# zx81_SD_12.net
KiCad netlist of a schematic drawn in EAGLE
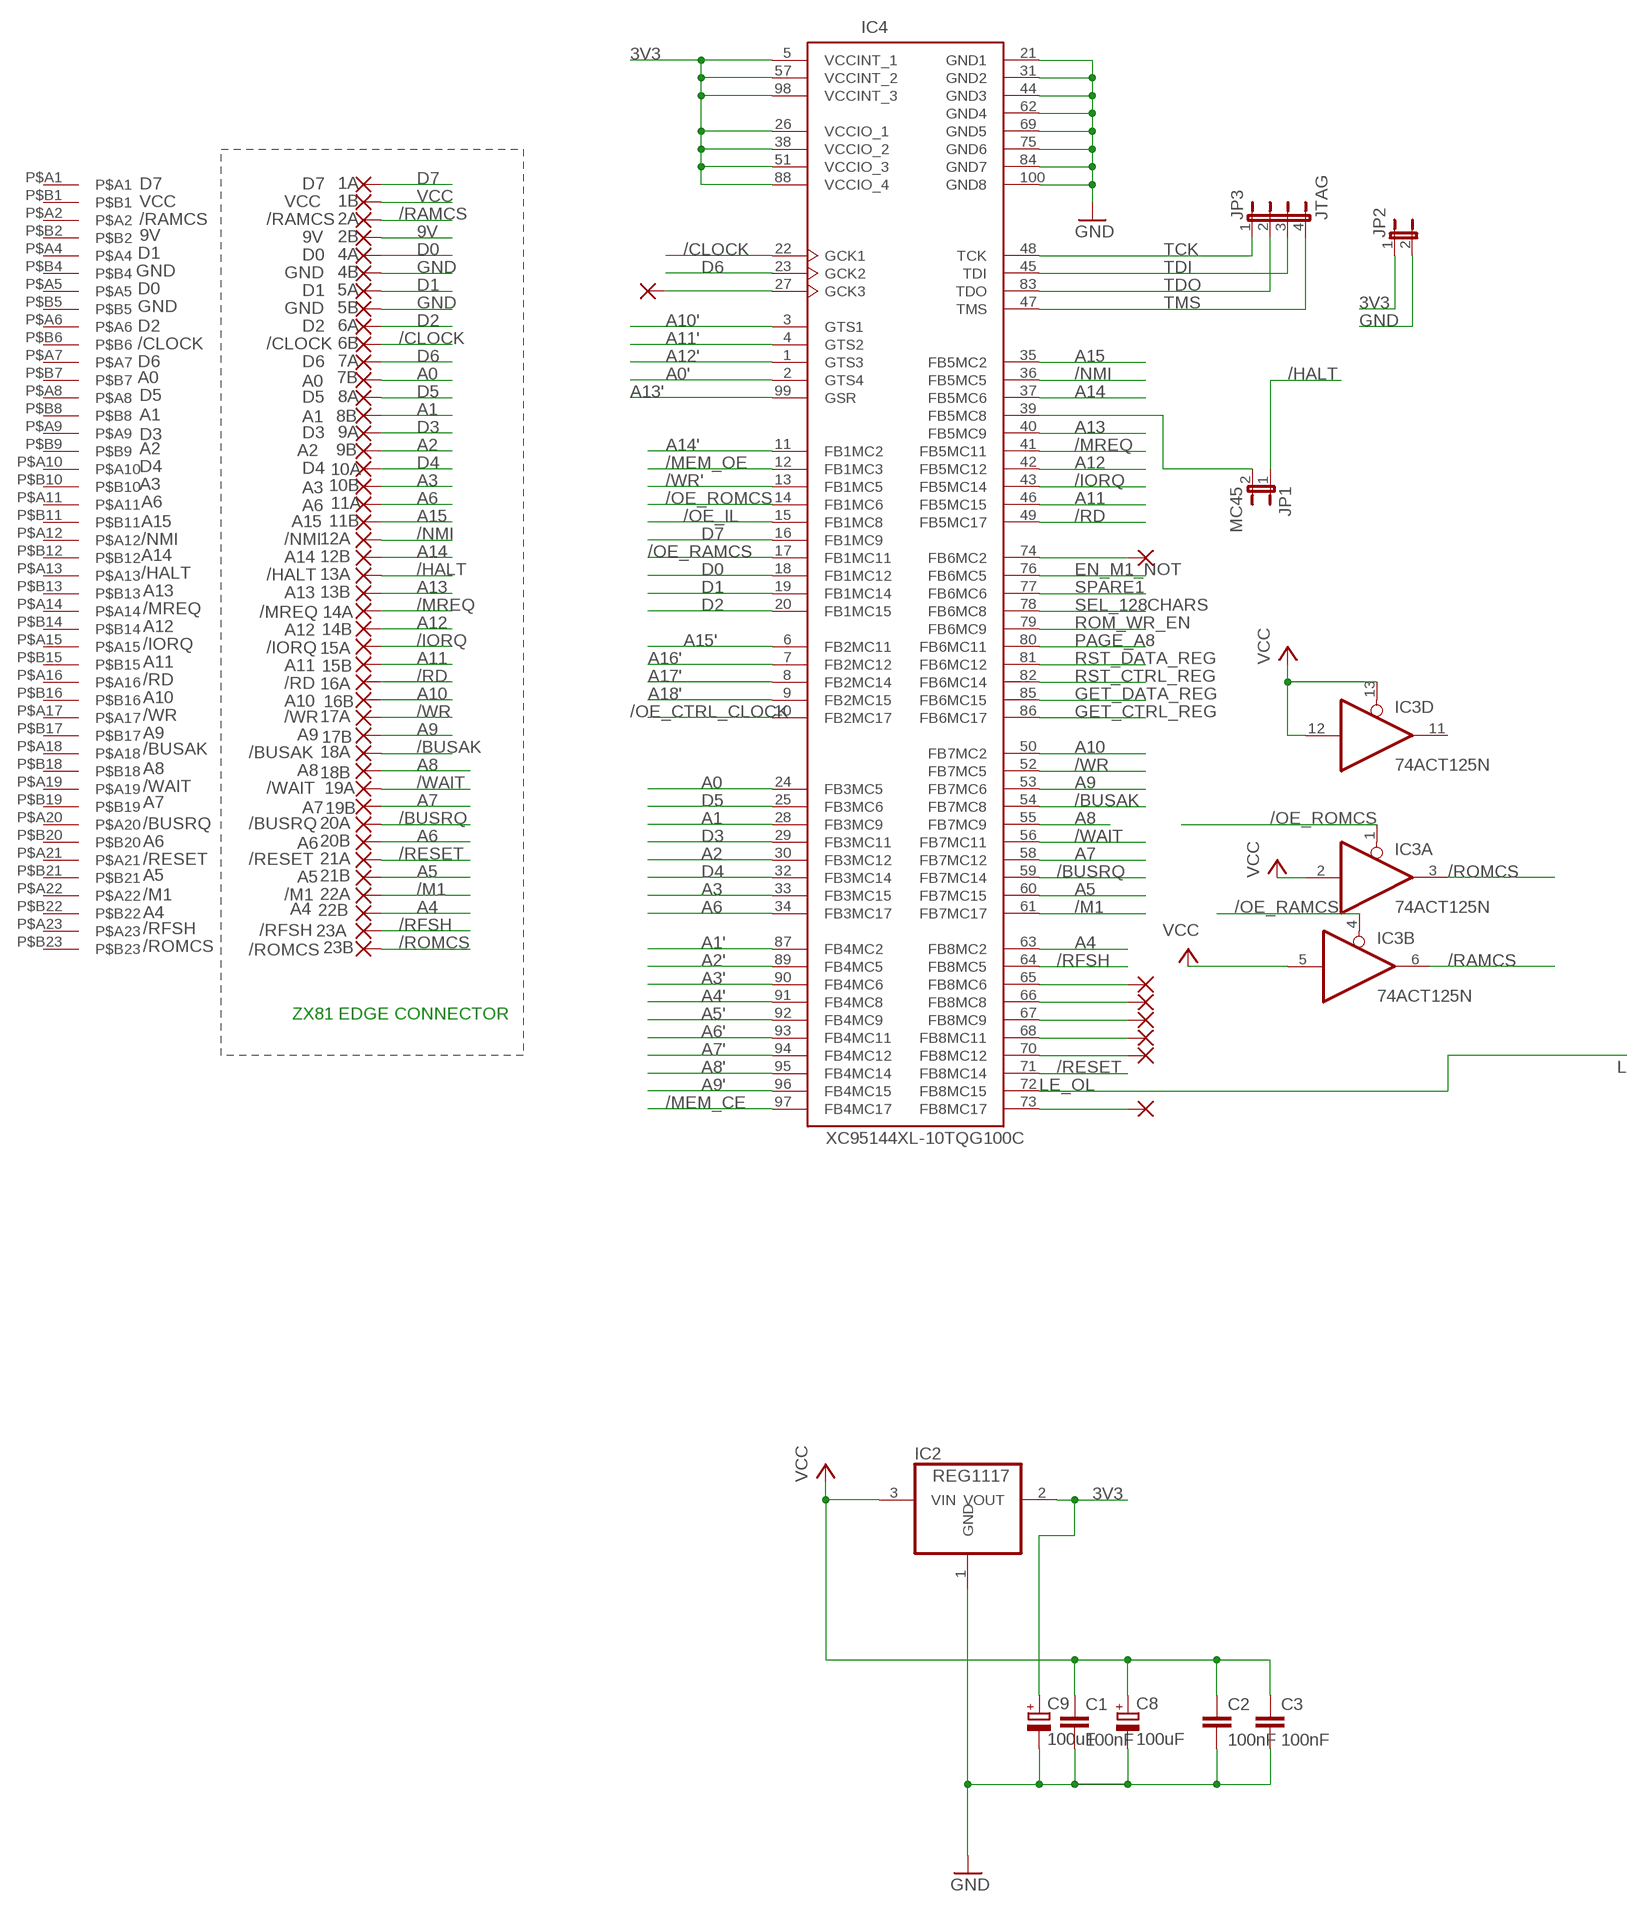
[diagram p0: schematic, sheet 1, part 1 of 2]
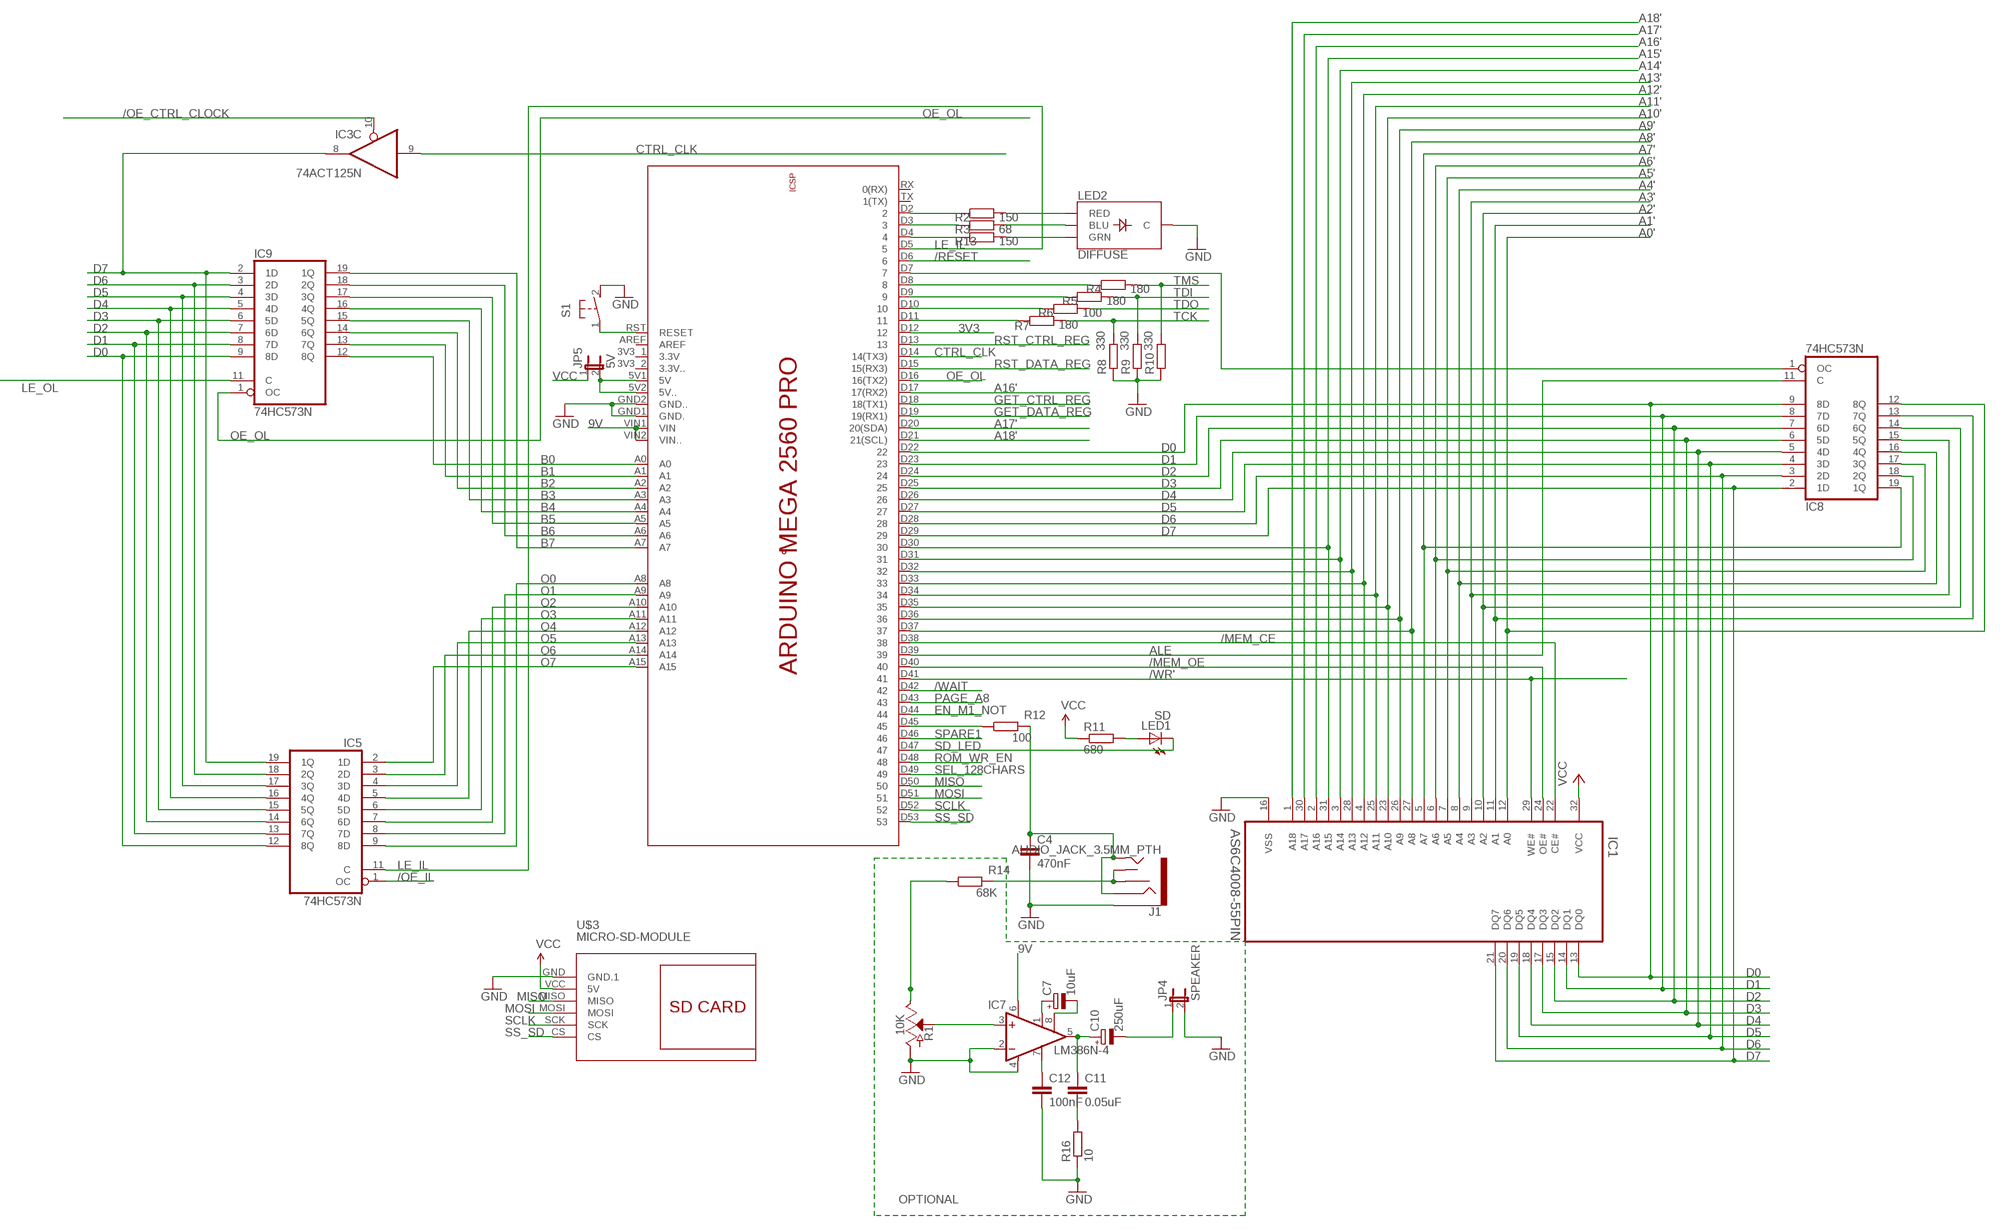
[diagram p1: schematic, sheet 1, part 2 of 2]

(export (version "E")
  (design (tool "Eeschema 10.0.6"))
  (components
    (comp (ref "1A")
      (value "D7")
      (footprint "eagle-import:EDGEPIN")
      (libsource (lib "eagle-import") (part "SMD2EDGEPIN"))
    )
    (comp (ref "1B")
      (value "VCC")
      (footprint "eagle-import:EDGEPIN")
      (libsource (lib "eagle-import") (part "SMD2EDGEPIN"))
    )
    (comp (ref "2A")
      (value "/RAMCS")
      (footprint "eagle-import:EDGEPIN")
      (libsource (lib "eagle-import") (part "SMD2EDGEPIN"))
    )
    (comp (ref "2B")
      (value "9V")
      (footprint "eagle-import:EDGEPIN")
      (libsource (lib "eagle-import") (part "SMD2EDGEPIN"))
    )
    (comp (ref "4A")
      (value "D0")
      (footprint "eagle-import:EDGEPIN")
      (libsource (lib "eagle-import") (part "SMD2EDGEPIN"))
    )
    (comp (ref "4B")
      (value "GND")
      (footprint "eagle-import:EDGEPIN")
      (libsource (lib "eagle-import") (part "SMD2EDGEPIN"))
    )
    (comp (ref "5A")
      (value "D1")
      (footprint "eagle-import:EDGEPIN")
      (libsource (lib "eagle-import") (part "SMD2EDGEPIN"))
    )
    (comp (ref "5B")
      (value "GND")
      (footprint "eagle-import:EDGEPIN")
      (libsource (lib "eagle-import") (part "SMD2EDGEPIN"))
    )
    (comp (ref "6A")
      (value "D2")
      (footprint "eagle-import:EDGEPIN")
      (libsource (lib "eagle-import") (part "SMD2EDGEPIN"))
    )
    (comp (ref "6B")
      (value "/CLOCK")
      (footprint "eagle-import:EDGEPIN")
      (libsource (lib "eagle-import") (part "SMD2EDGEPIN"))
    )
    (comp (ref "7A")
      (value "D6")
      (footprint "eagle-import:EDGEPIN")
      (libsource (lib "eagle-import") (part "SMD2EDGEPIN"))
    )
    (comp (ref "7B")
      (value "A0")
      (footprint "eagle-import:EDGEPIN")
      (libsource (lib "eagle-import") (part "SMD2EDGEPIN"))
    )
    (comp (ref "8A")
      (value "D5")
      (footprint "eagle-import:EDGEPIN")
      (libsource (lib "eagle-import") (part "SMD2EDGEPIN"))
    )
    (comp (ref "8B")
      (value "A1")
      (footprint "eagle-import:EDGEPIN")
      (libsource (lib "eagle-import") (part "SMD2EDGEPIN"))
    )
    (comp (ref "9A")
      (value "D3")
      (footprint "eagle-import:EDGEPIN")
      (libsource (lib "eagle-import") (part "SMD2EDGEPIN"))
    )
    (comp (ref "9B")
      (value "A2")
      (footprint "eagle-import:EDGEPIN")
      (libsource (lib "eagle-import") (part "SMD2EDGEPIN"))
    )
    (comp (ref "10A")
      (value "D4")
      (footprint "eagle-import:EDGEPIN")
      (libsource (lib "eagle-import") (part "SMD2EDGEPIN"))
    )
    (comp (ref "10B")
      (value "A3")
      (footprint "eagle-import:EDGEPIN")
      (libsource (lib "eagle-import") (part "SMD2EDGEPIN"))
    )
    (comp (ref "11A")
      (value "A6")
      (footprint "eagle-import:EDGEPIN")
      (libsource (lib "eagle-import") (part "SMD2EDGEPIN"))
    )
    (comp (ref "11B")
      (value "A15")
      (footprint "eagle-import:EDGEPIN")
      (libsource (lib "eagle-import") (part "SMD2EDGEPIN"))
    )
    (comp (ref "12A")
      (value "/NMI")
      (footprint "eagle-import:EDGEPIN")
      (libsource (lib "eagle-import") (part "SMD2EDGEPIN"))
    )
    (comp (ref "12B")
      (value "A14")
      (footprint "eagle-import:EDGEPIN")
      (libsource (lib "eagle-import") (part "SMD2EDGEPIN"))
    )
    (comp (ref "13A")
      (value "/HALT")
      (footprint "eagle-import:EDGEPIN")
      (libsource (lib "eagle-import") (part "SMD2EDGEPIN"))
    )
    (comp (ref "13B")
      (value "A13")
      (footprint "eagle-import:EDGEPIN")
      (libsource (lib "eagle-import") (part "SMD2EDGEPIN"))
    )
    (comp (ref "14A")
      (value "/MREQ")
      (footprint "eagle-import:EDGEPIN")
      (libsource (lib "eagle-import") (part "SMD2EDGEPIN"))
    )
    (comp (ref "14B")
      (value "A12")
      (footprint "eagle-import:EDGEPIN")
      (libsource (lib "eagle-import") (part "SMD2EDGEPIN"))
    )
    (comp (ref "15A")
      (value "/IORQ")
      (footprint "eagle-import:EDGEPIN")
      (libsource (lib "eagle-import") (part "SMD2EDGEPIN"))
    )
    (comp (ref "15B")
      (value "A11")
      (footprint "eagle-import:EDGEPIN")
      (libsource (lib "eagle-import") (part "SMD2EDGEPIN"))
    )
    (comp (ref "16A")
      (value "/RD")
      (footprint "eagle-import:EDGEPIN")
      (libsource (lib "eagle-import") (part "SMD2EDGEPIN"))
    )
    (comp (ref "16B")
      (value "A10")
      (footprint "eagle-import:EDGEPIN")
      (libsource (lib "eagle-import") (part "SMD2EDGEPIN"))
    )
    (comp (ref "17A")
      (value "/WR")
      (footprint "eagle-import:EDGEPIN")
      (libsource (lib "eagle-import") (part "SMD2EDGEPIN"))
    )
    (comp (ref "17B")
      (value "A9")
      (footprint "eagle-import:EDGEPIN")
      (libsource (lib "eagle-import") (part "SMD2EDGEPIN"))
    )
    (comp (ref "18A")
      (value "/BUSAK")
      (footprint "eagle-import:EDGEPIN")
      (libsource (lib "eagle-import") (part "SMD2EDGEPIN"))
    )
    (comp (ref "18B")
      (value "A8")
      (footprint "eagle-import:EDGEPIN")
      (libsource (lib "eagle-import") (part "SMD2EDGEPIN"))
    )
    (comp (ref "19A")
      (value "/WAIT")
      (footprint "eagle-import:EDGEPIN")
      (libsource (lib "eagle-import") (part "SMD2EDGEPIN"))
    )
    (comp (ref "19B")
      (value "A7")
      (footprint "eagle-import:EDGEPIN")
      (libsource (lib "eagle-import") (part "SMD2EDGEPIN"))
    )
    (comp (ref "20A")
      (value "/BUSRQ")
      (footprint "eagle-import:EDGEPIN")
      (libsource (lib "eagle-import") (part "SMD2EDGEPIN"))
    )
    (comp (ref "20B")
      (value "A6")
      (footprint "eagle-import:EDGEPIN")
      (libsource (lib "eagle-import") (part "SMD2EDGEPIN"))
    )
    (comp (ref "21A")
      (value "/RESET")
      (footprint "eagle-import:EDGEPIN")
      (libsource (lib "eagle-import") (part "SMD2EDGEPIN"))
    )
    (comp (ref "21B")
      (value "A5")
      (footprint "eagle-import:EDGEPIN")
      (libsource (lib "eagle-import") (part "SMD2EDGEPIN"))
    )
    (comp (ref "22A")
      (value "/M1")
      (footprint "eagle-import:EDGEPIN")
      (libsource (lib "eagle-import") (part "SMD2EDGEPIN"))
    )
    (comp (ref "22B")
      (value "A4")
      (footprint "eagle-import:EDGEPIN")
      (libsource (lib "eagle-import") (part "SMD2EDGEPIN"))
    )
    (comp (ref "23A")
      (value "/RFSH")
      (footprint "eagle-import:EDGEPIN")
      (libsource (lib "eagle-import") (part "SMD2EDGEPIN"))
    )
    (comp (ref "23B")
      (value "/ROMCS")
      (footprint "eagle-import:EDGEPIN")
      (libsource (lib "eagle-import") (part "SMD2EDGEPIN"))
    )
    (comp (ref "C1")
      (value "100nF")
      (footprint "eagle-import:C025-040X050")
      (libsource (lib "eagle-import") (part "C-EU025-040X050"))
    )
    (comp (ref "C2")
      (value "100nF")
      (footprint "eagle-import:C025-040X050")
      (libsource (lib "eagle-import") (part "C-EU025-040X050"))
    )
    (comp (ref "C3")
      (value "100nF")
      (footprint "eagle-import:C025-040X050")
      (libsource (lib "eagle-import") (part "C-EU025-040X050"))
    )
    (comp (ref "C4")
      (value "470nF")
      (footprint "eagle-import:C025-040X050")
      (libsource (lib "eagle-import") (part "C-EU025-040X050"))
    )
    (comp (ref "C7")
      (value "10uF")
      (footprint "eagle-import:E2-5")
      (libsource (lib "eagle-import") (part "CPOL-EUE2-5"))
    )
    (comp (ref "C8")
      (value "100uF")
      (footprint "eagle-import:E2-5")
      (libsource (lib "eagle-import") (part "CPOL-EUE2-5"))
    )
    (comp (ref "C9")
      (value "100uF")
      (footprint "eagle-import:E2-5")
      (libsource (lib "eagle-import") (part "CPOL-EUE2-5"))
    )
    (comp (ref "C10")
      (value "250uF")
      (footprint "eagle-import:E2-5")
      (libsource (lib "eagle-import") (part "CPOL-EUE2-5"))
    )
    (comp (ref "C11")
      (value "0.05uF")
      (footprint "eagle-import:C025-040X050")
      (libsource (lib "eagle-import") (part "C-EU025-040X050"))
    )
    (comp (ref "C12")
      (value "100nF")
      (footprint "eagle-import:C025-040X050")
      (libsource (lib "eagle-import") (part "C-EU025-040X050"))
    )
    (comp (ref "IC1")
      (value "AS6C4008-55PIN")
      (footprint "eagle-import:DIP1524W45P254L4203H406Q32")
      (fields (field (name "MF") "Alliance"))
      (libsource (lib "eagle-import") (part "AS6C4008-55PIN"))
    )
    (comp (ref "IC2")
      (value "REG1117")
      (footprint "eagle-import:SOT223")
      (libsource (lib "eagle-import") (part "REG1117"))
    )
    (comp (ref "IC3")
      (value "74ACT125N")
      (footprint "eagle-import:DIL14")
      (libsource (lib "eagle-import") (part "74125NACT"))
    )
    (comp (ref "IC4")
      (value "XC95144XL-10TQG100C")
      (footprint "eagle-import:TQFP100")
      (fields (field (name "MF") "Xilinx Inc."))
      (libsource (lib "eagle-import") (part "XC95144XL-10TQG100C"))
    )
    (comp (ref "IC5")
      (value "74HC573N")
      (footprint "eagle-import:DIL20")
      (libsource (lib "eagle-import") (part "74573NHC"))
    )
    (comp (ref "IC7")
      (value "LM386N-4")
      (footprint "eagle-import:DIL08")
      (libsource (lib "eagle-import") (part "LM386?-N4"))
    )
    (comp (ref "IC8")
      (value "74HC573N")
      (footprint "eagle-import:DIL20")
      (libsource (lib "eagle-import") (part "74573NHC"))
    )
    (comp (ref "IC9")
      (value "74HC573N")
      (footprint "eagle-import:DIL20")
      (libsource (lib "eagle-import") (part "74573NHC"))
    )
    (comp (ref "J1")
      (value "AUDIO_JACK_3.5MM_PTH")
      (footprint "eagle-import:AUDIO-JACK")
      (libsource (lib "eagle-import") (part "AUDIO_JACK_3.5MM_PTH"))
    )
    (comp (ref "JP1")
      (value "MC45")
      (footprint "eagle-import:JP1")
      (libsource (lib "eagle-import") (part "JP1E"))
    )
    (comp (ref "JP2")
      (value "JP1E")
      (footprint "eagle-import:JP1")
      (libsource (lib "eagle-import") (part "JP1E"))
    )
    (comp (ref "JP3")
      (value "JTAG")
      (footprint "eagle-import:JP4")
      (libsource (lib "eagle-import") (part "JP4E"))
    )
    (comp (ref "JP4")
      (value "SPEAKER")
      (footprint "eagle-import:JP1")
      (libsource (lib "eagle-import") (part "JP1E"))
    )
    (comp (ref "JP5")
      (value "5V")
      (footprint "eagle-import:JP1")
      (libsource (lib "eagle-import") (part "JP1E"))
    )
    (comp (ref "LED1")
      (value "SD")
      (footprint "eagle-import:LED5MM")
      (libsource (lib "eagle-import") (part "LED5MM"))
    )
    (comp (ref "LED2")
      (value "DIFFUSE")
      (footprint "eagle-import:LED-RGB-THRU")
      (libsource (lib "eagle-import") (part "LED-RGB-CCDIFFUSE"))
    )
    (comp (ref "PAD1")
      (value "1,6/0,8")
      (footprint "eagle-import:1,6_0,8")
      (libsource (lib "eagle-import") (part "1,6/0,8"))
    )
    (comp (ref "PAD2")
      (value "1,6/0,8")
      (footprint "eagle-import:1,6_0,8")
      (libsource (lib "eagle-import") (part "1,6/0,8"))
    )
    (comp (ref "PAD3")
      (value "1,6/0,8")
      (footprint "eagle-import:1,6_0,8")
      (libsource (lib "eagle-import") (part "1,6/0,8"))
    )
    (comp (ref "PAD4")
      (value "1,6/0,8")
      (footprint "eagle-import:1,6_0,8")
      (libsource (lib "eagle-import") (part "1,6/0,8"))
    )
    (comp (ref "PAD5")
      (value "1,6/0,8")
      (footprint "eagle-import:1,6_0,8")
      (libsource (lib "eagle-import") (part "1,6/0,8"))
    )
    (comp (ref "PAD6")
      (value "1,6/0,8")
      (footprint "eagle-import:1,6_0,8")
      (libsource (lib "eagle-import") (part "1,6/0,8"))
    )
    (comp (ref "PAD7")
      (value "1,6/0,8")
      (footprint "eagle-import:1,6_0,8")
      (libsource (lib "eagle-import") (part "1,6/0,8"))
    )
    (comp (ref "PAD8")
      (value "1,6/0,8")
      (footprint "eagle-import:1,6_0,8")
      (libsource (lib "eagle-import") (part "1,6/0,8"))
    )
    (comp (ref "R1")
      (value "10K")
      (footprint "eagle-import:POT-WHEEL")
      (libsource (lib "eagle-import") (part "POT"))
    )
    (comp (ref "R2")
      (value "150")
      (footprint "eagle-import:0204_7")
      (libsource (lib "eagle-import") (part "rcl_334_R-EU_0204/7"))
    )
    (comp (ref "R3")
      (value "68")
      (footprint "eagle-import:0204_7")
      (libsource (lib "eagle-import") (part "rcl_334_R-EU_0204/7"))
    )
    (comp (ref "R4")
      (value "180")
      (footprint "eagle-import:0204_7")
      (libsource (lib "eagle-import") (part "rcl_334_R-EU_0204/7"))
    )
    (comp (ref "R5")
      (value "180")
      (footprint "eagle-import:0204_7")
      (libsource (lib "eagle-import") (part "rcl_334_R-EU_0204/7"))
    )
    (comp (ref "R6")
      (value "100")
      (footprint "eagle-import:0204_7")
      (libsource (lib "eagle-import") (part "rcl_334_R-EU_0204/7"))
    )
    (comp (ref "R7")
      (value "180")
      (footprint "eagle-import:0204_7")
      (libsource (lib "eagle-import") (part "rcl_334_R-EU_0204/7"))
    )
    (comp (ref "R8")
      (value "330")
      (footprint "eagle-import:0204_7")
      (libsource (lib "eagle-import") (part "rcl_334_R-EU_0204/7"))
    )
    (comp (ref "R9")
      (value "330")
      (footprint "eagle-import:0204_7")
      (libsource (lib "eagle-import") (part "rcl_334_R-EU_0204/7"))
    )
    (comp (ref "R10")
      (value "330")
      (footprint "eagle-import:0204_7")
      (libsource (lib "eagle-import") (part "rcl_334_R-EU_0204/7"))
    )
    (comp (ref "R11")
      (value "680")
      (footprint "eagle-import:0204_7")
      (libsource (lib "eagle-import") (part "R-EU_0204/7"))
    )
    (comp (ref "R12")
      (value "100")
      (footprint "eagle-import:0204_7")
      (libsource (lib "eagle-import") (part "R-EU_0204/7"))
    )
    (comp (ref "R13")
      (value "150")
      (footprint "eagle-import:0204_7")
      (libsource (lib "eagle-import") (part "rcl_334_R-EU_0204/7"))
    )
    (comp (ref "R14")
      (value "68K")
      (footprint "eagle-import:0204_7")
      (libsource (lib "eagle-import") (part "R-EU_0204/7"))
    )
    (comp (ref "R16")
      (value "10")
      (footprint "eagle-import:0204_7")
      (libsource (lib "eagle-import") (part "R-EU_0204/7"))
    )
    (comp (ref "S1")
      (value "31-XX")
      (footprint "eagle-import:B3F-31XX")
      (fields (field (name "MPN") "B3F-3100"))
      (libsource (lib "eagle-import") (part "31-XX"))
    )
    (comp (ref "U$1")
      (value "ZX81_EDGE")
      (footprint "eagle-import:ZX81_IFACE")
      (libsource (lib "eagle-import") (part "ZX81_EDGE"))
    )
    (comp (ref "U$2")
      (value "E14_ARDUINO_REVC_ARDUINO_MEGA2560_PRO")
      (footprint "eagle-import:E14_ARDUINO_REVC_ARDUINO_MEGA2560_PRO")
      (libsource (lib "eagle-import") (part "E14_ARDUINO_REVC_ARDUINO_MEGA2560_PRO"))
    )
    (comp (ref "U$3")
      (value "MICRO-SD-MODULE")
      (footprint "eagle-import:MICROSD-MODULE")
      (libsource (lib "eagle-import") (part "MICRO-SD-MODULE"))
    )
  )
  (nets
    (net (code "1") (name "/3V3") (class "Default")
      (node (ref "C9") (pin "+") (pinfunction "+_+") (pintype "passive"))
      (node (ref "IC2") (pin "2") (pinfunction "VOUT_2") (pintype "output"))
      (node (ref "IC4") (pin "26") (pinfunction "VCCIO_1_26") (pintype "power_in"))
      (node (ref "IC4") (pin "38") (pinfunction "VCCIO_2_38") (pintype "power_in"))
      (node (ref "IC4") (pin "5") (pinfunction "VCCINT_1_5") (pintype "power_in"))
      (node (ref "IC4") (pin "51") (pinfunction "VCCIO_3_51") (pintype "power_in"))
      (node (ref "IC4") (pin "57") (pinfunction "VCCINT_2_57") (pintype "power_in"))
      (node (ref "IC4") (pin "88") (pinfunction "VCCIO_4_88") (pintype "power_in"))
      (node (ref "IC4") (pin "98") (pinfunction "VCCINT_3_98") (pintype "power_in"))
      (node (ref "JP2") (pin "1") (pinfunction "1_1") (pintype "passive"))
      (node (ref "U$2") (pin "D12") (pinfunction "12_D12") (pintype "bidirectional"))
    )
    (net (code "2") (name "/9V") (class "Default")
      (node (ref "2B") (pin "1") (pinfunction "P_1") (pintype "passive"))
      (node (ref "IC7") (pin "6") (pinfunction "VS_6") (pintype "power_in"))
      (node (ref "U$2") (pin "VIN1") (pinfunction "VIN_VIN1") (pintype "bidirectional"))
      (node (ref "U$2") (pin "VIN2") (pinfunction "VIN.._VIN2") (pintype "bidirectional"))
    )
    (net (code "3") (name "/A0") (class "Default")
      (node (ref "7B") (pin "1") (pinfunction "P_1") (pintype "passive"))
      (node (ref "IC4") (pin "24") (pinfunction "FB3MC5_24") (pintype "bidirectional"))
    )
    (net (code "4") (name "/A0'") (class "Default")
      (node (ref "IC1") (pin "12") (pinfunction "A0_12") (pintype "input"))
      (node (ref "IC4") (pin "2") (pinfunction "GTS4_2") (pintype "bidirectional"))
      (node (ref "IC8") (pin "12") (pinfunction "8Q_12") (pintype "tri_state"))
    )
    (net (code "5") (name "/A1") (class "Default")
      (node (ref "8B") (pin "1") (pinfunction "P_1") (pintype "passive"))
      (node (ref "IC4") (pin "28") (pinfunction "FB3MC9_28") (pintype "bidirectional"))
    )
    (net (code "6") (name "/A1'") (class "Default")
      (node (ref "IC1") (pin "11") (pinfunction "A1_11") (pintype "input"))
      (node (ref "IC4") (pin "87") (pinfunction "FB4MC2_87") (pintype "bidirectional"))
      (node (ref "IC8") (pin "13") (pinfunction "7Q_13") (pintype "tri_state"))
    )
    (net (code "7") (name "/A2") (class "Default")
      (node (ref "9B") (pin "1") (pinfunction "P_1") (pintype "passive"))
      (node (ref "IC4") (pin "30") (pinfunction "FB3MC12_30") (pintype "bidirectional"))
    )
    (net (code "8") (name "/A2'") (class "Default")
      (node (ref "IC1") (pin "10") (pinfunction "A2_10") (pintype "input"))
      (node (ref "IC4") (pin "89") (pinfunction "FB4MC5_89") (pintype "bidirectional"))
      (node (ref "IC8") (pin "14") (pinfunction "6Q_14") (pintype "tri_state"))
    )
    (net (code "9") (name "/A3") (class "Default")
      (node (ref "10B") (pin "1") (pinfunction "P_1") (pintype "passive"))
      (node (ref "IC4") (pin "33") (pinfunction "FB3MC15_33") (pintype "bidirectional"))
    )
    (net (code "10") (name "/A3'") (class "Default")
      (node (ref "IC1") (pin "9") (pinfunction "A3_9") (pintype "input"))
      (node (ref "IC4") (pin "90") (pinfunction "FB4MC6_90") (pintype "bidirectional"))
      (node (ref "IC8") (pin "15") (pinfunction "5Q_15") (pintype "tri_state"))
    )
    (net (code "11") (name "/A4") (class "Default")
      (node (ref "22B") (pin "1") (pinfunction "P_1") (pintype "passive"))
      (node (ref "IC4") (pin "63") (pinfunction "FB8MC2_63") (pintype "bidirectional"))
    )
    (net (code "12") (name "/A4'") (class "Default")
      (node (ref "IC1") (pin "8") (pinfunction "A4_8") (pintype "input"))
      (node (ref "IC4") (pin "91") (pinfunction "FB4MC8_91") (pintype "bidirectional"))
      (node (ref "IC8") (pin "16") (pinfunction "4Q_16") (pintype "tri_state"))
    )
    (net (code "13") (name "/A5") (class "Default")
      (node (ref "21B") (pin "1") (pinfunction "P_1") (pintype "passive"))
      (node (ref "IC4") (pin "60") (pinfunction "FB7MC15_60") (pintype "bidirectional"))
    )
    (net (code "14") (name "/A5'") (class "Default")
      (node (ref "IC1") (pin "7") (pinfunction "A5_7") (pintype "input"))
      (node (ref "IC4") (pin "92") (pinfunction "FB4MC9_92") (pintype "bidirectional"))
      (node (ref "IC8") (pin "17") (pinfunction "3Q_17") (pintype "tri_state"))
    )
    (net (code "15") (name "/A6") (class "Default")
      (node (ref "11A") (pin "1") (pinfunction "P_1") (pintype "passive"))
      (node (ref "20B") (pin "1") (pinfunction "P_1") (pintype "passive"))
      (node (ref "IC4") (pin "34") (pinfunction "FB3MC17_34") (pintype "bidirectional"))
    )
    (net (code "16") (name "/A6'") (class "Default")
      (node (ref "IC1") (pin "6") (pinfunction "A6_6") (pintype "input"))
      (node (ref "IC4") (pin "93") (pinfunction "FB4MC11_93") (pintype "bidirectional"))
      (node (ref "IC8") (pin "18") (pinfunction "2Q_18") (pintype "tri_state"))
    )
    (net (code "17") (name "/A7") (class "Default")
      (node (ref "19B") (pin "1") (pinfunction "P_1") (pintype "passive"))
      (node (ref "IC4") (pin "58") (pinfunction "FB7MC12_58") (pintype "bidirectional"))
    )
    (net (code "18") (name "/A7'") (class "Default")
      (node (ref "IC1") (pin "5") (pinfunction "A7_5") (pintype "input"))
      (node (ref "IC4") (pin "94") (pinfunction "FB4MC12_94") (pintype "bidirectional"))
      (node (ref "IC8") (pin "19") (pinfunction "1Q_19") (pintype "tri_state"))
    )
    (net (code "19") (name "/A8") (class "Default")
      (node (ref "18B") (pin "1") (pinfunction "P_1") (pintype "passive"))
      (node (ref "IC4") (pin "55") (pinfunction "FB7MC9_55") (pintype "bidirectional"))
    )
    (net (code "20") (name "/A8'") (class "Default")
      (node (ref "IC1") (pin "27") (pinfunction "A8_27") (pintype "input"))
      (node (ref "IC4") (pin "95") (pinfunction "FB4MC14_95") (pintype "bidirectional"))
      (node (ref "U$2") (pin "D37") (pinfunction "37_D37") (pintype "bidirectional"))
    )
    (net (code "21") (name "/A9") (class "Default")
      (node (ref "17B") (pin "1") (pinfunction "P_1") (pintype "passive"))
      (node (ref "IC4") (pin "53") (pinfunction "FB7MC6_53") (pintype "bidirectional"))
    )
    (net (code "22") (name "/A9'") (class "Default")
      (node (ref "IC1") (pin "26") (pinfunction "A9_26") (pintype "input"))
      (node (ref "IC4") (pin "96") (pinfunction "FB4MC15_96") (pintype "bidirectional"))
      (node (ref "U$2") (pin "D36") (pinfunction "36_D36") (pintype "bidirectional"))
    )
    (net (code "23") (name "/A10") (class "Default")
      (node (ref "16B") (pin "1") (pinfunction "P_1") (pintype "passive"))
      (node (ref "IC4") (pin "50") (pinfunction "FB7MC2_50") (pintype "bidirectional"))
    )
    (net (code "24") (name "/A10'") (class "Default")
      (node (ref "IC1") (pin "23") (pinfunction "A10_23") (pintype "input"))
      (node (ref "IC4") (pin "3") (pinfunction "GTS1_3") (pintype "bidirectional"))
      (node (ref "U$2") (pin "D35") (pinfunction "35_D35") (pintype "bidirectional"))
    )
    (net (code "25") (name "/A11") (class "Default")
      (node (ref "15B") (pin "1") (pinfunction "P_1") (pintype "passive"))
      (node (ref "IC4") (pin "46") (pinfunction "FB5MC15_46") (pintype "bidirectional"))
    )
    (net (code "26") (name "/A11'") (class "Default")
      (node (ref "IC1") (pin "25") (pinfunction "A11_25") (pintype "input"))
      (node (ref "IC4") (pin "4") (pinfunction "GTS2_4") (pintype "bidirectional"))
      (node (ref "U$2") (pin "D34") (pinfunction "34_D34") (pintype "bidirectional"))
    )
    (net (code "27") (name "/A12") (class "Default")
      (node (ref "14B") (pin "1") (pinfunction "P_1") (pintype "passive"))
      (node (ref "IC4") (pin "42") (pinfunction "FB5MC12_42") (pintype "bidirectional"))
    )
    (net (code "28") (name "/A12'") (class "Default")
      (node (ref "IC1") (pin "4") (pinfunction "A12_4") (pintype "input"))
      (node (ref "IC4") (pin "1") (pinfunction "GTS3_1") (pintype "bidirectional"))
      (node (ref "U$2") (pin "D33") (pinfunction "33_D33") (pintype "bidirectional"))
    )
    (net (code "29") (name "/A13") (class "Default")
      (node (ref "13B") (pin "1") (pinfunction "P_1") (pintype "passive"))
      (node (ref "IC4") (pin "40") (pinfunction "FB5MC9_40") (pintype "bidirectional"))
    )
    (net (code "30") (name "/A13'") (class "Default")
      (node (ref "IC1") (pin "28") (pinfunction "A13_28") (pintype "input"))
      (node (ref "IC4") (pin "99") (pinfunction "GSR_99") (pintype "bidirectional"))
      (node (ref "U$2") (pin "D32") (pinfunction "32_D32") (pintype "bidirectional"))
    )
    (net (code "31") (name "/A14") (class "Default")
      (node (ref "12B") (pin "1") (pinfunction "P_1") (pintype "passive"))
      (node (ref "IC4") (pin "37") (pinfunction "FB5MC6_37") (pintype "bidirectional"))
    )
    (net (code "32") (name "/A14'") (class "Default")
      (node (ref "IC1") (pin "3") (pinfunction "A14_3") (pintype "input"))
      (node (ref "IC4") (pin "11") (pinfunction "FB1MC2_11") (pintype "bidirectional"))
      (node (ref "U$2") (pin "D31") (pinfunction "31_D31") (pintype "bidirectional"))
    )
    (net (code "33") (name "/A15") (class "Default")
      (node (ref "11B") (pin "1") (pinfunction "P_1") (pintype "passive"))
      (node (ref "IC4") (pin "35") (pinfunction "FB5MC2_35") (pintype "bidirectional"))
    )
    (net (code "34") (name "/A15'") (class "Default")
      (node (ref "IC1") (pin "31") (pinfunction "A15_31") (pintype "input"))
      (node (ref "IC4") (pin "6") (pinfunction "FB2MC11_6") (pintype "bidirectional"))
      (node (ref "U$2") (pin "D30") (pinfunction "30_D30") (pintype "bidirectional"))
    )
    (net (code "35") (name "/A16'") (class "Default")
      (node (ref "IC1") (pin "2") (pinfunction "A16_2") (pintype "input"))
      (node (ref "IC4") (pin "7") (pinfunction "FB2MC12_7") (pintype "bidirectional"))
      (node (ref "U$2") (pin "D17") (pinfunction "17(RX2)_D17") (pintype "bidirectional"))
    )
    (net (code "36") (name "/A17'") (class "Default")
      (node (ref "IC1") (pin "30") (pinfunction "A17_30") (pintype "input"))
      (node (ref "IC4") (pin "8") (pinfunction "FB2MC14_8") (pintype "bidirectional"))
      (node (ref "U$2") (pin "D20") (pinfunction "20(SDA)_D20") (pintype "bidirectional"))
    )
    (net (code "37") (name "/A18'") (class "Default")
      (node (ref "IC1") (pin "1") (pinfunction "A18_1") (pintype "input"))
      (node (ref "IC4") (pin "9") (pinfunction "FB2MC15_9") (pintype "bidirectional"))
      (node (ref "U$2") (pin "D21") (pinfunction "21(SCL)_D21") (pintype "bidirectional"))
    )
    (net (code "38") (name "/ALE") (class "Default")
      (node (ref "IC8") (pin "11") (pinfunction "C_11") (pintype "input"))
      (node (ref "U$2") (pin "D39") (pinfunction "39_D39") (pintype "bidirectional"))
    )
    (net (code "39") (name "/B0") (class "Default")
      (node (ref "IC9") (pin "19") (pinfunction "1Q_19") (pintype "tri_state"))
      (node (ref "U$2") (pin "A7") (pinfunction "A7_A7") (pintype "bidirectional"))
    )
    (net (code "40") (name "/B1") (class "Default")
      (node (ref "IC9") (pin "18") (pinfunction "2Q_18") (pintype "tri_state"))
      (node (ref "U$2") (pin "A6") (pinfunction "A6_A6") (pintype "bidirectional"))
    )
    (net (code "41") (name "/B2") (class "Default")
      (node (ref "IC9") (pin "17") (pinfunction "3Q_17") (pintype "tri_state"))
      (node (ref "U$2") (pin "A5") (pinfunction "A5_A5") (pintype "bidirectional"))
    )
    (net (code "42") (name "/B3") (class "Default")
      (node (ref "IC9") (pin "16") (pinfunction "4Q_16") (pintype "tri_state"))
      (node (ref "U$2") (pin "A4") (pinfunction "A4_A4") (pintype "bidirectional"))
    )
    (net (code "43") (name "/B4") (class "Default")
      (node (ref "IC9") (pin "15") (pinfunction "5Q_15") (pintype "tri_state"))
      (node (ref "U$2") (pin "A3") (pinfunction "A3_A3") (pintype "bidirectional"))
    )
    (net (code "44") (name "/B5") (class "Default")
      (node (ref "IC9") (pin "14") (pinfunction "6Q_14") (pintype "tri_state"))
      (node (ref "U$2") (pin "A2") (pinfunction "A2_A2") (pintype "bidirectional"))
    )
    (net (code "45") (name "/B6") (class "Default")
      (node (ref "IC9") (pin "13") (pinfunction "7Q_13") (pintype "tri_state"))
      (node (ref "U$2") (pin "A1") (pinfunction "A1_A1") (pintype "bidirectional"))
    )
    (net (code "46") (name "/B7") (class "Default")
      (node (ref "IC9") (pin "12") (pinfunction "8Q_12") (pintype "tri_state"))
      (node (ref "U$2") (pin "A0") (pinfunction "A0_A0") (pintype "bidirectional"))
    )
    (net (code "47") (name "/CTRL_CLK") (class "Default")
      (node (ref "IC3") (pin "9") (pinfunction "I_9") (pintype "input"))
      (node (ref "U$2") (pin "D14") (pinfunction "14(TX3)_D14") (pintype "bidirectional"))
    )
    (net (code "48") (name "/D0") (class "Default")
      (node (ref "4A") (pin "1") (pinfunction "P_1") (pintype "passive"))
      (node (ref "IC1") (pin "13") (pinfunction "DQ0_13") (pintype "bidirectional"))
      (node (ref "IC4") (pin "18") (pinfunction "FB1MC12_18") (pintype "bidirectional"))
      (node (ref "IC5") (pin "12") (pinfunction "8Q_12") (pintype "tri_state"))
      (node (ref "IC8") (pin "9") (pinfunction "8D_9") (pintype "input"))
      (node (ref "IC9") (pin "9") (pinfunction "8D_9") (pintype "input"))
      (node (ref "U$2") (pin "D22") (pinfunction "22_D22") (pintype "bidirectional"))
    )
    (net (code "49") (name "/D1") (class "Default")
      (node (ref "5A") (pin "1") (pinfunction "P_1") (pintype "passive"))
      (node (ref "IC1") (pin "14") (pinfunction "DQ1_14") (pintype "bidirectional"))
      (node (ref "IC4") (pin "19") (pinfunction "FB1MC14_19") (pintype "bidirectional"))
      (node (ref "IC5") (pin "13") (pinfunction "7Q_13") (pintype "tri_state"))
      (node (ref "IC8") (pin "8") (pinfunction "7D_8") (pintype "input"))
      (node (ref "IC9") (pin "8") (pinfunction "7D_8") (pintype "input"))
      (node (ref "U$2") (pin "D23") (pinfunction "23_D23") (pintype "bidirectional"))
    )
    (net (code "50") (name "/D2") (class "Default")
      (node (ref "6A") (pin "1") (pinfunction "P_1") (pintype "passive"))
      (node (ref "IC1") (pin "15") (pinfunction "DQ2_15") (pintype "bidirectional"))
      (node (ref "IC4") (pin "20") (pinfunction "FB1MC15_20") (pintype "bidirectional"))
      (node (ref "IC5") (pin "14") (pinfunction "6Q_14") (pintype "tri_state"))
      (node (ref "IC8") (pin "7") (pinfunction "6D_7") (pintype "input"))
      (node (ref "IC9") (pin "7") (pinfunction "6D_7") (pintype "input"))
      (node (ref "U$2") (pin "D24") (pinfunction "24_D24") (pintype "bidirectional"))
    )
    (net (code "51") (name "/D3") (class "Default")
      (node (ref "9A") (pin "1") (pinfunction "P_1") (pintype "passive"))
      (node (ref "IC1") (pin "17") (pinfunction "DQ3_17") (pintype "bidirectional"))
      (node (ref "IC4") (pin "29") (pinfunction "FB3MC11_29") (pintype "bidirectional"))
      (node (ref "IC5") (pin "15") (pinfunction "5Q_15") (pintype "tri_state"))
      (node (ref "IC8") (pin "6") (pinfunction "5D_6") (pintype "input"))
      (node (ref "IC9") (pin "6") (pinfunction "5D_6") (pintype "input"))
      (node (ref "U$2") (pin "D25") (pinfunction "25_D25") (pintype "bidirectional"))
    )
    (net (code "52") (name "/D4") (class "Default")
      (node (ref "10A") (pin "1") (pinfunction "P_1") (pintype "passive"))
      (node (ref "IC1") (pin "18") (pinfunction "DQ4_18") (pintype "bidirectional"))
      (node (ref "IC4") (pin "32") (pinfunction "FB3MC14_32") (pintype "bidirectional"))
      (node (ref "IC5") (pin "16") (pinfunction "4Q_16") (pintype "tri_state"))
      (node (ref "IC8") (pin "5") (pinfunction "4D_5") (pintype "input"))
      (node (ref "IC9") (pin "5") (pinfunction "4D_5") (pintype "input"))
      (node (ref "U$2") (pin "D26") (pinfunction "26_D26") (pintype "bidirectional"))
    )
    (net (code "53") (name "/D5") (class "Default")
      (node (ref "8A") (pin "1") (pinfunction "P_1") (pintype "passive"))
      (node (ref "IC1") (pin "19") (pinfunction "DQ5_19") (pintype "bidirectional"))
      (node (ref "IC4") (pin "25") (pinfunction "FB3MC6_25") (pintype "bidirectional"))
      (node (ref "IC5") (pin "17") (pinfunction "3Q_17") (pintype "tri_state"))
      (node (ref "IC8") (pin "4") (pinfunction "3D_4") (pintype "input"))
      (node (ref "IC9") (pin "4") (pinfunction "3D_4") (pintype "input"))
      (node (ref "U$2") (pin "D27") (pinfunction "27_D27") (pintype "bidirectional"))
    )
    (net (code "54") (name "/D6") (class "Default")
      (node (ref "7A") (pin "1") (pinfunction "P_1") (pintype "passive"))
      (node (ref "IC1") (pin "20") (pinfunction "DQ6_20") (pintype "bidirectional"))
      (node (ref "IC4") (pin "23") (pinfunction "GCK2_23") (pintype "bidirectional"))
      (node (ref "IC5") (pin "18") (pinfunction "2Q_18") (pintype "tri_state"))
      (node (ref "IC8") (pin "3") (pinfunction "2D_3") (pintype "input"))
      (node (ref "IC9") (pin "3") (pinfunction "2D_3") (pintype "input"))
      (node (ref "U$2") (pin "D28") (pinfunction "28_D28") (pintype "bidirectional"))
    )
    (net (code "55") (name "/D7") (class "Default")
      (node (ref "1A") (pin "1") (pinfunction "P_1") (pintype "passive"))
      (node (ref "IC1") (pin "21") (pinfunction "DQ7_21") (pintype "bidirectional"))
      (node (ref "IC3") (pin "8") (pinfunction "O_8") (pintype "tri_state"))
      (node (ref "IC4") (pin "16") (pinfunction "FB1MC9_16") (pintype "bidirectional"))
      (node (ref "IC5") (pin "19") (pinfunction "1Q_19") (pintype "tri_state"))
      (node (ref "IC8") (pin "2") (pinfunction "1D_2") (pintype "input"))
      (node (ref "IC9") (pin "2") (pinfunction "1D_2") (pintype "input"))
      (node (ref "U$2") (pin "D29") (pinfunction "29_D29") (pintype "bidirectional"))
    )
    (net (code "56") (name "/EN_M1_NOT") (class "Default")
      (node (ref "IC4") (pin "76") (pinfunction "FB6MC5_76") (pintype "bidirectional"))
      (node (ref "U$2") (pin "D44") (pinfunction "44_D44") (pintype "bidirectional"))
    )
    (net (code "57") (name "/GET_CTRL_REG") (class "Default")
      (node (ref "IC4") (pin "86") (pinfunction "FB6MC17_86") (pintype "bidirectional"))
      (node (ref "U$2") (pin "D18") (pinfunction "18(TX1)_D18") (pintype "bidirectional"))
    )
    (net (code "58") (name "/GET_DATA_REG") (class "Default")
      (node (ref "IC4") (pin "85") (pinfunction "FB6MC15_85") (pintype "bidirectional"))
      (node (ref "U$2") (pin "D19") (pinfunction "19(RX1)_D19") (pintype "bidirectional"))
    )
    (net (code "59") (name "/LE_IL") (class "Default")
      (node (ref "IC5") (pin "11") (pinfunction "C_11") (pintype "input"))
      (node (ref "U$2") (pin "D5") (pinfunction "5_D5") (pintype "bidirectional"))
    )
    (net (code "60") (name "/LE_OL") (class "Default")
      (node (ref "IC4") (pin "72") (pinfunction "FB8MC15_72") (pintype "bidirectional"))
      (node (ref "IC9") (pin "11") (pinfunction "C_11") (pintype "input"))
    )
    (net (code "61") (name "/MISO") (class "Default")
      (node (ref "U$2") (pin "D50") (pinfunction "50_D50") (pintype "bidirectional"))
      (node (ref "U$3") (pin "MISO") (pinfunction "MISO_MISO") (pintype "bidirectional"))
    )
    (net (code "62") (name "/MOSI") (class "Default")
      (node (ref "U$2") (pin "D51") (pinfunction "51_D51") (pintype "bidirectional"))
      (node (ref "U$3") (pin "MOSI") (pinfunction "MOSI_MOSI") (pintype "bidirectional"))
    )
    (net (code "63") (name "/O0") (class "Default")
      (node (ref "IC5") (pin "2") (pinfunction "1D_2") (pintype "input"))
      (node (ref "U$2") (pin "A15") (pinfunction "A15_A15") (pintype "bidirectional"))
    )
    (net (code "64") (name "/O1") (class "Default")
      (node (ref "IC5") (pin "3") (pinfunction "2D_3") (pintype "input"))
      (node (ref "U$2") (pin "A14") (pinfunction "A14_A14") (pintype "bidirectional"))
    )
    (net (code "65") (name "/O2") (class "Default")
      (node (ref "IC5") (pin "4") (pinfunction "3D_4") (pintype "input"))
      (node (ref "U$2") (pin "A13") (pinfunction "A13_A13") (pintype "bidirectional"))
    )
    (net (code "66") (name "/O3") (class "Default")
      (node (ref "IC5") (pin "5") (pinfunction "4D_5") (pintype "input"))
      (node (ref "U$2") (pin "A12") (pinfunction "A12_A12") (pintype "bidirectional"))
    )
    (net (code "67") (name "/O4") (class "Default")
      (node (ref "IC5") (pin "6") (pinfunction "5D_6") (pintype "input"))
      (node (ref "U$2") (pin "A11") (pinfunction "A11_A11") (pintype "bidirectional"))
    )
    (net (code "68") (name "/O5") (class "Default")
      (node (ref "IC5") (pin "7") (pinfunction "6D_7") (pintype "input"))
      (node (ref "U$2") (pin "A10") (pinfunction "A10_A10") (pintype "bidirectional"))
    )
    (net (code "69") (name "/O6") (class "Default")
      (node (ref "IC5") (pin "8") (pinfunction "7D_8") (pintype "input"))
      (node (ref "U$2") (pin "A9") (pinfunction "A9_A9") (pintype "bidirectional"))
    )
    (net (code "70") (name "/O7") (class "Default")
      (node (ref "IC5") (pin "9") (pinfunction "8D_9") (pintype "input"))
      (node (ref "U$2") (pin "A8") (pinfunction "A8_A8") (pintype "bidirectional"))
    )
    (net (code "71") (name "/OE_OL") (class "Default")
      (node (ref "IC9") (pin "1") (pinfunction "OC_1") (pintype "input"))
      (node (ref "U$2") (pin "D16") (pinfunction "16(TX2)_D16") (pintype "bidirectional"))
    )
    (net (code "72") (name "/PAGE_A8") (class "Default")
      (node (ref "IC4") (pin "80") (pinfunction "FB6MC11_80") (pintype "bidirectional"))
      (node (ref "U$2") (pin "D43") (pinfunction "43_D43") (pintype "bidirectional"))
    )
    (net (code "73") (name "/ROM_WR_EN") (class "Default")
      (node (ref "IC4") (pin "79") (pinfunction "FB6MC9_79") (pintype "bidirectional"))
      (node (ref "U$2") (pin "D48") (pinfunction "48_D48") (pintype "bidirectional"))
    )
    (net (code "74") (name "/RST_CTRL_REG") (class "Default")
      (node (ref "IC4") (pin "82") (pinfunction "FB6MC14_82") (pintype "bidirectional"))
      (node (ref "U$2") (pin "D13") (pinfunction "13_D13") (pintype "bidirectional"))
    )
    (net (code "75") (name "/RST_DATA_REG") (class "Default")
      (node (ref "IC4") (pin "81") (pinfunction "FB6MC12_81") (pintype "bidirectional"))
      (node (ref "U$2") (pin "D15") (pinfunction "15(RX3)_D15") (pintype "bidirectional"))
    )
    (net (code "76") (name "/SCLK") (class "Default")
      (node (ref "U$2") (pin "D52") (pinfunction "52_D52") (pintype "bidirectional"))
      (node (ref "U$3") (pin "SCK") (pinfunction "SCK_SCK") (pintype "bidirectional"))
    )
    (net (code "77") (name "/SD_LED") (class "Default")
      (node (ref "LED1") (pin "K") (pinfunction "C_K") (pintype "passive"))
      (node (ref "U$2") (pin "D47") (pinfunction "47_D47") (pintype "bidirectional"))
    )
    (net (code "78") (name "/SEL_128CHARS") (class "Default")
      (node (ref "IC4") (pin "78") (pinfunction "FB6MC8_78") (pintype "bidirectional"))
      (node (ref "U$2") (pin "D49") (pinfunction "49_D49") (pintype "bidirectional"))
    )
    (net (code "79") (name "/SPARE1") (class "Default")
      (node (ref "IC4") (pin "77") (pinfunction "FB6MC6_77") (pintype "bidirectional"))
      (node (ref "U$2") (pin "D46") (pinfunction "46_D46") (pintype "bidirectional"))
    )
    (net (code "80") (name "/SS_SD") (class "Default")
      (node (ref "U$2") (pin "D53") (pinfunction "53_D53") (pintype "bidirectional"))
      (node (ref "U$3") (pin "CS") (pinfunction "CS_CS") (pintype "bidirectional"))
    )
    (net (code "81") (name "/TCK") (class "Default")
      (node (ref "IC4") (pin "48") (pinfunction "TCK_48") (pintype "passive"))
      (node (ref "JP3") (pin "1") (pinfunction "1_1") (pintype "passive"))
      (node (ref "R7") (pin "2") (pinfunction "2_2") (pintype "passive"))
      (node (ref "R8") (pin "2") (pinfunction "2_2") (pintype "passive"))
    )
    (net (code "82") (name "/TDI") (class "Default")
      (node (ref "IC4") (pin "45") (pinfunction "TDI_45") (pintype "passive"))
      (node (ref "JP3") (pin "3") (pinfunction "3_3") (pintype "passive"))
      (node (ref "R5") (pin "2") (pinfunction "2_2") (pintype "passive"))
      (node (ref "R9") (pin "2") (pinfunction "2_2") (pintype "passive"))
    )
    (net (code "83") (name "/TDO") (class "Default")
      (node (ref "IC4") (pin "83") (pinfunction "TDO_83") (pintype "passive"))
      (node (ref "JP3") (pin "2") (pinfunction "2_2") (pintype "passive"))
      (node (ref "R6") (pin "2") (pinfunction "2_2") (pintype "passive"))
    )
    (net (code "84") (name "/TMS") (class "Default")
      (node (ref "IC4") (pin "47") (pinfunction "TMS_47") (pintype "passive"))
      (node (ref "JP3") (pin "4") (pinfunction "4_4") (pintype "passive"))
      (node (ref "R10") (pin "2") (pinfunction "2_2") (pintype "passive"))
      (node (ref "R4") (pin "2") (pinfunction "2_2") (pintype "passive"))
    )
    (net (code "85") (name "/{slash}BUSAK") (class "Default")
      (node (ref "18A") (pin "1") (pinfunction "P_1") (pintype "passive"))
      (node (ref "IC4") (pin "54") (pinfunction "FB7MC8_54") (pintype "bidirectional"))
    )
    (net (code "86") (name "/{slash}BUSRQ") (class "Default")
      (node (ref "20A") (pin "1") (pinfunction "P_1") (pintype "passive"))
      (node (ref "IC4") (pin "59") (pinfunction "FB7MC14_59") (pintype "bidirectional"))
    )
    (net (code "87") (name "/{slash}CLOCK") (class "Default")
      (node (ref "6B") (pin "1") (pinfunction "P_1") (pintype "passive"))
      (node (ref "IC4") (pin "22") (pinfunction "GCK1_22") (pintype "bidirectional"))
    )
    (net (code "88") (name "/{slash}HALT") (class "Default")
      (node (ref "13A") (pin "1") (pinfunction "P_1") (pintype "passive"))
      (node (ref "JP1") (pin "1") (pinfunction "1_1") (pintype "passive"))
    )
    (net (code "89") (name "/{slash}IORQ") (class "Default")
      (node (ref "15A") (pin "1") (pinfunction "P_1") (pintype "passive"))
      (node (ref "IC4") (pin "43") (pinfunction "FB5MC14_43") (pintype "bidirectional"))
    )
    (net (code "90") (name "/{slash}M1") (class "Default")
      (node (ref "22A") (pin "1") (pinfunction "P_1") (pintype "passive"))
      (node (ref "IC4") (pin "61") (pinfunction "FB7MC17_61") (pintype "bidirectional"))
    )
    (net (code "91") (name "/{slash}MEM_CE") (class "Default")
      (node (ref "IC1") (pin "22") (pinfunction "CE#_22") (pintype "input"))
      (node (ref "IC4") (pin "97") (pinfunction "FB4MC17_97") (pintype "bidirectional"))
      (node (ref "U$2") (pin "D38") (pinfunction "38_D38") (pintype "bidirectional"))
    )
    (net (code "92") (name "/{slash}MEM_OE") (class "Default")
      (node (ref "IC1") (pin "24") (pinfunction "OE#_24") (pintype "input"))
      (node (ref "IC4") (pin "12") (pinfunction "FB1MC3_12") (pintype "bidirectional"))
      (node (ref "U$2") (pin "D40") (pinfunction "40_D40") (pintype "bidirectional"))
    )
    (net (code "93") (name "/{slash}MREQ") (class "Default")
      (node (ref "14A") (pin "1") (pinfunction "P_1") (pintype "passive"))
      (node (ref "IC4") (pin "41") (pinfunction "FB5MC11_41") (pintype "bidirectional"))
    )
    (net (code "94") (name "/{slash}NMI") (class "Default")
      (node (ref "12A") (pin "1") (pinfunction "P_1") (pintype "passive"))
      (node (ref "IC4") (pin "36") (pinfunction "FB5MC5_36") (pintype "bidirectional"))
    )
    (net (code "95") (name "/{slash}OE_CTRL_CLOCK") (class "Default")
      (node (ref "IC3") (pin "10") (pinfunction "OE_10") (pintype "input"))
      (node (ref "IC4") (pin "10") (pinfunction "FB2MC17_10") (pintype "bidirectional"))
    )
    (net (code "96") (name "/{slash}OE_IL") (class "Default")
      (node (ref "IC4") (pin "15") (pinfunction "FB1MC8_15") (pintype "bidirectional"))
      (node (ref "IC5") (pin "1") (pinfunction "OC_1") (pintype "input"))
    )
    (net (code "97") (name "/{slash}OE_RAMCS") (class "Default")
      (node (ref "IC3") (pin "4") (pinfunction "OE_4") (pintype "input"))
      (node (ref "IC4") (pin "17") (pinfunction "FB1MC11_17") (pintype "bidirectional"))
    )
    (net (code "98") (name "/{slash}OE_ROMCS") (class "Default")
      (node (ref "IC3") (pin "1") (pinfunction "OE_1") (pintype "input"))
      (node (ref "IC4") (pin "14") (pinfunction "FB1MC6_14") (pintype "bidirectional"))
    )
    (net (code "99") (name "/{slash}RAMCS") (class "Default")
      (node (ref "2A") (pin "1") (pinfunction "P_1") (pintype "passive"))
      (node (ref "IC3") (pin "6") (pinfunction "O_6") (pintype "tri_state"))
    )
    (net (code "100") (name "/{slash}RD") (class "Default")
      (node (ref "16A") (pin "1") (pinfunction "P_1") (pintype "passive"))
      (node (ref "IC4") (pin "49") (pinfunction "FB5MC17_49") (pintype "bidirectional"))
    )
    (net (code "101") (name "/{slash}RESET") (class "Default")
      (node (ref "21A") (pin "1") (pinfunction "P_1") (pintype "passive"))
      (node (ref "IC4") (pin "71") (pinfunction "FB8MC14_71") (pintype "bidirectional"))
      (node (ref "U$2") (pin "D6") (pinfunction "6_D6") (pintype "bidirectional"))
    )
    (net (code "102") (name "/{slash}RFSH") (class "Default")
      (node (ref "23A") (pin "1") (pinfunction "P_1") (pintype "passive"))
      (node (ref "IC4") (pin "64") (pinfunction "FB8MC5_64") (pintype "bidirectional"))
    )
    (net (code "103") (name "/{slash}ROMCS") (class "Default")
      (node (ref "23B") (pin "1") (pinfunction "P_1") (pintype "passive"))
      (node (ref "IC3") (pin "3") (pinfunction "O_3") (pintype "tri_state"))
    )
    (net (code "104") (name "/{slash}WAIT") (class "Default")
      (node (ref "19A") (pin "1") (pinfunction "P_1") (pintype "passive"))
      (node (ref "IC4") (pin "56") (pinfunction "FB7MC11_56") (pintype "bidirectional"))
      (node (ref "U$2") (pin "D42") (pinfunction "42_D42") (pintype "bidirectional"))
    )
    (net (code "105") (name "/{slash}WR") (class "Default")
      (node (ref "17A") (pin "1") (pinfunction "P_1") (pintype "passive"))
      (node (ref "IC4") (pin "52") (pinfunction "FB7MC5_52") (pintype "bidirectional"))
    )
    (net (code "106") (name "/{slash}WR'") (class "Default")
      (node (ref "IC1") (pin "29") (pinfunction "WE#_29") (pintype "input"))
      (node (ref "IC4") (pin "13") (pinfunction "FB1MC5_13") (pintype "bidirectional"))
      (node (ref "U$2") (pin "D41") (pinfunction "41_D41") (pintype "bidirectional"))
    )
    (net (code "107") (name "GND") (class "Default")
      (node (ref "4B") (pin "1") (pinfunction "P_1") (pintype "passive"))
      (node (ref "5B") (pin "1") (pinfunction "P_1") (pintype "passive"))
      (node (ref "C1") (pin "2") (pinfunction "2_2") (pintype "passive"))
      (node (ref "C12") (pin "2") (pinfunction "2_2") (pintype "passive"))
      (node (ref "C2") (pin "2") (pinfunction "2_2") (pintype "passive"))
      (node (ref "C3") (pin "2") (pinfunction "2_2") (pintype "passive"))
      (node (ref "C4") (pin "2") (pinfunction "2_2") (pintype "passive"))
      (node (ref "C8") (pin "-") (pinfunction "-_-") (pintype "passive"))
      (node (ref "C9") (pin "-") (pinfunction "-_-") (pintype "passive"))
      (node (ref "IC1") (pin "16") (pinfunction "VSS_16") (pintype "power_in"))
      (node (ref "IC2") (pin "1") (pinfunction "GND_1") (pintype "power_in"))
      (node (ref "IC4") (pin "100") (pinfunction "GND8_100") (pintype "power_in"))
      (node (ref "IC4") (pin "21") (pinfunction "GND1_21") (pintype "power_in"))
      (node (ref "IC4") (pin "31") (pinfunction "GND2_31") (pintype "power_in"))
      (node (ref "IC4") (pin "44") (pinfunction "GND3_44") (pintype "power_in"))
      (node (ref "IC4") (pin "62") (pinfunction "GND4_62") (pintype "power_in"))
      (node (ref "IC4") (pin "69") (pinfunction "GND5_69") (pintype "power_in"))
      (node (ref "IC4") (pin "75") (pinfunction "GND6_75") (pintype "power_in"))
      (node (ref "IC4") (pin "84") (pinfunction "GND7_84") (pintype "power_in"))
      (node (ref "IC7") (pin "2") (pinfunction "-IN_2") (pintype "input"))
      (node (ref "IC7") (pin "4") (pinfunction "GND_4") (pintype "power_in"))
      (node (ref "J1") (pin "SLEEVE") (pinfunction "SLEEVE_SLEEVE") (pintype "bidirectional"))
      (node (ref "JP2") (pin "2") (pinfunction "2_2") (pintype "passive"))
      (node (ref "JP4") (pin "2") (pinfunction "2_2") (pintype "passive"))
      (node (ref "LED2") (pin "2") (pinfunction "C_2") (pintype "bidirectional"))
      (node (ref "R1") (pin "P$1") (pinfunction "A_P$1") (pintype "passive"))
      (node (ref "R10") (pin "1") (pinfunction "1_1") (pintype "passive"))
      (node (ref "R16") (pin "1") (pinfunction "1_1") (pintype "passive"))
      (node (ref "R8") (pin "1") (pinfunction "1_1") (pintype "passive"))
      (node (ref "R9") (pin "1") (pinfunction "1_1") (pintype "passive"))
      (node (ref "S1") (pin "2") (pinfunction "S_2") (pintype "passive"))
      (node (ref "U$2") (pin "GND1") (pinfunction "GND._GND1") (pintype "bidirectional"))
      (node (ref "U$2") (pin "GND2") (pinfunction "GND.._GND2") (pintype "bidirectional"))
      (node (ref "U$3") (pin "GND") (pinfunction "GND.1_GND") (pintype "power_in"))
    )
    (net (code "108") (name "Net-(C4-Pad1)") (class "Default")
      (node (ref "C4") (pin "1") (pinfunction "1_1") (pintype "passive"))
      (node (ref "J1") (pin "RING") (pinfunction "RING_RING") (pintype "bidirectional"))
      (node (ref "J1") (pin "TIP") (pinfunction "TIP_TIP") (pintype "bidirectional"))
      (node (ref "R12") (pin "2") (pinfunction "2_2") (pintype "passive"))
    )
    (net (code "109") (name "Net-(C7-Pad+)") (class "Default")
      (node (ref "C7") (pin "+") (pinfunction "+_+") (pintype "passive"))
      (node (ref "IC7") (pin "1") (pinfunction "GAIN_1") (pintype "passive"))
    )
    (net (code "110") (name "Net-(C7-Pad-)") (class "Default")
      (node (ref "C7") (pin "-") (pinfunction "-_-") (pintype "passive"))
      (node (ref "IC7") (pin "8") (pinfunction "GAIN_8") (pintype "passive"))
    )
    (net (code "111") (name "Net-(C10-Pad-)") (class "Default")
      (node (ref "C10") (pin "-") (pinfunction "-_-") (pintype "passive"))
      (node (ref "JP4") (pin "1") (pinfunction "1_1") (pintype "passive"))
    )
    (net (code "112") (name "Net-(C11-Pad2)") (class "Default")
      (node (ref "C11") (pin "2") (pinfunction "2_2") (pintype "passive"))
      (node (ref "R16") (pin "2") (pinfunction "2_2") (pintype "passive"))
    )
    (net (code "113") (name "Net-(IC4-FB5MC8)") (class "Default")
      (node (ref "IC4") (pin "39") (pinfunction "FB5MC8_39") (pintype "bidirectional"))
      (node (ref "JP1") (pin "2") (pinfunction "2_2") (pintype "passive"))
    )
    (net (code "114") (name "Net-(IC4-FB6MC2)") (class "Default")
      (node (ref "IC4") (pin "74") (pinfunction "FB6MC2_74") (pintype "bidirectional"))
      (node (ref "PAD8") (pin "1") (pinfunction "P_1") (pintype "passive"))
    )
    (net (code "115") (name "Net-(IC4-FB8MC6)") (class "Default")
      (node (ref "IC4") (pin "65") (pinfunction "FB8MC6_65") (pintype "bidirectional"))
      (node (ref "PAD2") (pin "1") (pinfunction "P_1") (pintype "passive"))
    )
    (net (code "116") (name "Net-(IC4-FB8MC8)") (class "Default")
      (node (ref "IC4") (pin "66") (pinfunction "FB8MC8_66") (pintype "bidirectional"))
      (node (ref "PAD3") (pin "1") (pinfunction "P_1") (pintype "passive"))
    )
    (net (code "117") (name "Net-(IC4-FB8MC9)") (class "Default")
      (node (ref "IC4") (pin "67") (pinfunction "FB8MC9_67") (pintype "bidirectional"))
      (node (ref "PAD4") (pin "1") (pinfunction "P_1") (pintype "passive"))
    )
    (net (code "118") (name "Net-(IC4-FB8MC11)") (class "Default")
      (node (ref "IC4") (pin "68") (pinfunction "FB8MC11_68") (pintype "bidirectional"))
      (node (ref "PAD5") (pin "1") (pinfunction "P_1") (pintype "passive"))
    )
    (net (code "119") (name "Net-(IC4-FB8MC12)") (class "Default")
      (node (ref "IC4") (pin "70") (pinfunction "FB8MC12_70") (pintype "bidirectional"))
      (node (ref "PAD7") (pin "1") (pinfunction "P_1") (pintype "passive"))
    )
    (net (code "120") (name "Net-(IC4-FB8MC17)") (class "Default")
      (node (ref "IC4") (pin "73") (pinfunction "FB8MC17_73") (pintype "bidirectional"))
      (node (ref "PAD6") (pin "1") (pinfunction "P_1") (pintype "passive"))
    )
    (net (code "121") (name "Net-(IC4-GCK3)") (class "Default")
      (node (ref "IC4") (pin "27") (pinfunction "GCK3_27") (pintype "bidirectional"))
      (node (ref "PAD1") (pin "1") (pinfunction "P_1") (pintype "passive"))
    )
    (net (code "122") (name "Net-(IC7-+IN)") (class "Default")
      (node (ref "IC7") (pin "3") (pinfunction "+IN_3") (pintype "input"))
      (node (ref "R1") (pin "P$3") (pinfunction "S_P$3") (pintype "passive"))
    )
    (net (code "123") (name "Net-(IC7-BYPASS)") (class "Default")
      (node (ref "C12") (pin "1") (pinfunction "1_1") (pintype "passive"))
      (node (ref "IC7") (pin "7") (pinfunction "BYPASS_7") (pintype "passive"))
    )
    (net (code "124") (name "Net-(IC7-OUT)") (class "Default")
      (node (ref "C10") (pin "+") (pinfunction "+_+") (pintype "passive"))
      (node (ref "C11") (pin "1") (pinfunction "1_1") (pintype "passive"))
      (node (ref "IC7") (pin "5") (pinfunction "OUT_5") (pintype "output"))
    )
    (net (code "125") (name "Net-(IC8A-OC)") (class "Default")
      (node (ref "IC8") (pin "1") (pinfunction "OC_1") (pintype "input"))
      (node (ref "U$2") (pin "D7") (pinfunction "7_D7") (pintype "bidirectional"))
    )
    (net (code "126") (name "Net-(J1-PadRSH)") (class "Default")
      (node (ref "J1") (pin "RSH") (pinfunction "RSH_RSH") (pintype "bidirectional"))
      (node (ref "J1") (pin "TSH") (pinfunction "TSH_TSH") (pintype "bidirectional"))
      (node (ref "R14") (pin "2") (pinfunction "2_2") (pintype "passive"))
    )
    (net (code "127") (name "Net-(LED1-PadA)") (class "Default")
      (node (ref "LED1") (pin "A") (pinfunction "A_A") (pintype "passive"))
      (node (ref "R11") (pin "2") (pinfunction "2_2") (pintype "passive"))
    )
    (net (code "128") (name "Net-(LED2-BLU)") (class "Default")
      (node (ref "LED2") (pin "4") (pinfunction "BLU_4") (pintype "bidirectional"))
      (node (ref "R3") (pin "2") (pinfunction "2_2") (pintype "passive"))
    )
    (net (code "129") (name "Net-(LED2-GRN)") (class "Default")
      (node (ref "LED2") (pin "3") (pinfunction "GRN_3") (pintype "bidirectional"))
      (node (ref "R13") (pin "2") (pinfunction "2_2") (pintype "passive"))
    )
    (net (code "130") (name "Net-(LED2-RED)") (class "Default")
      (node (ref "LED2") (pin "1") (pinfunction "RED_1") (pintype "bidirectional"))
      (node (ref "R2") (pin "2") (pinfunction "2_2") (pintype "passive"))
    )
    (net (code "131") (name "Net-(R1-E)") (class "Default")
      (node (ref "R1") (pin "P$2") (pinfunction "E_P$2") (pintype "passive"))
      (node (ref "R14") (pin "1") (pinfunction "1_1") (pintype "passive"))
    )
    (net (code "132") (name "Net-(S1-P)") (class "Default")
      (node (ref "S1") (pin "1") (pinfunction "P_1") (pintype "passive"))
      (node (ref "U$2") (pin "RST") (pinfunction "RESET_RST") (pintype "bidirectional"))
    )
    (net (code "133") (name "Net-(U$2-2)") (class "Default")
      (node (ref "R2") (pin "1") (pinfunction "1_1") (pintype "passive"))
      (node (ref "U$2") (pin "D2") (pinfunction "2_D2") (pintype "bidirectional"))
    )
    (net (code "134") (name "Net-(U$2-3)") (class "Default")
      (node (ref "R3") (pin "1") (pinfunction "1_1") (pintype "passive"))
      (node (ref "U$2") (pin "D3") (pinfunction "3_D3") (pintype "bidirectional"))
    )
    (net (code "135") (name "Net-(U$2-4)") (class "Default")
      (node (ref "R13") (pin "1") (pinfunction "1_1") (pintype "passive"))
      (node (ref "U$2") (pin "D4") (pinfunction "4_D4") (pintype "bidirectional"))
    )
    (net (code "136") (name "Net-(U$2-5V)") (class "Default")
      (node (ref "JP5") (pin "2") (pinfunction "2_2") (pintype "passive"))
      (node (ref "U$2") (pin "5V1") (pinfunction "5V_5V1") (pintype "bidirectional"))
      (node (ref "U$2") (pin "5V2") (pinfunction "5V.._5V2") (pintype "bidirectional"))
    )
    (net (code "137") (name "Net-(U$2-8)") (class "Default")
      (node (ref "R4") (pin "1") (pinfunction "1_1") (pintype "passive"))
      (node (ref "U$2") (pin "D8") (pinfunction "8_D8") (pintype "bidirectional"))
    )
    (net (code "138") (name "Net-(U$2-9)") (class "Default")
      (node (ref "R5") (pin "1") (pinfunction "1_1") (pintype "passive"))
      (node (ref "U$2") (pin "D9") (pinfunction "9_D9") (pintype "bidirectional"))
    )
    (net (code "139") (name "Net-(U$2-10)") (class "Default")
      (node (ref "R6") (pin "1") (pinfunction "1_1") (pintype "passive"))
      (node (ref "U$2") (pin "D10") (pinfunction "10_D10") (pintype "bidirectional"))
    )
    (net (code "140") (name "Net-(U$2-11)") (class "Default")
      (node (ref "R7") (pin "1") (pinfunction "1_1") (pintype "passive"))
      (node (ref "U$2") (pin "D11") (pinfunction "11_D11") (pintype "bidirectional"))
    )
    (net (code "141") (name "Net-(U$2-45)") (class "Default")
      (node (ref "R12") (pin "1") (pinfunction "1_1") (pintype "passive"))
      (node (ref "U$2") (pin "D45") (pinfunction "45_D45") (pintype "bidirectional"))
    )
    (net (code "142") (name "VCC") (class "Default")
      (node (ref "1B") (pin "1") (pinfunction "P_1") (pintype "passive"))
      (node (ref "C1") (pin "1") (pinfunction "1_1") (pintype "passive"))
      (node (ref "C2") (pin "1") (pinfunction "1_1") (pintype "passive"))
      (node (ref "C3") (pin "1") (pinfunction "1_1") (pintype "passive"))
      (node (ref "C8") (pin "+") (pinfunction "+_+") (pintype "passive"))
      (node (ref "IC1") (pin "32") (pinfunction "VCC_32") (pintype "power_in"))
      (node (ref "IC2") (pin "3") (pinfunction "VIN_3") (pintype "input"))
      (node (ref "IC3") (pin "12") (pinfunction "I_12") (pintype "input"))
      (node (ref "IC3") (pin "13") (pinfunction "OE_13") (pintype "input"))
      (node (ref "IC3") (pin "2") (pinfunction "I_2") (pintype "input"))
      (node (ref "IC3") (pin "5") (pinfunction "I_5") (pintype "input"))
      (node (ref "JP5") (pin "1") (pinfunction "1_1") (pintype "passive"))
      (node (ref "R11") (pin "1") (pinfunction "1_1") (pintype "passive"))
      (node (ref "U$3") (pin "VCC") (pinfunction "5V_VCC") (pintype "power_in"))
    )
    (net (code "143") (name "unconnected-(IC3D-O-Pad11)") (class "Default")
      (node (ref "IC3") (pin "11") (pinfunction "O_11") (pintype "tri_state"))
    )
    (net (code "144") (name "unconnected-(U$1-PadP$A1)") (class "Default")
      (node (ref "U$1") (pin "P$A1") (pinfunction "P$A1_P$A1") (pintype "bidirectional"))
    )
    (net (code "145") (name "unconnected-(U$1-PadP$A2)") (class "Default")
      (node (ref "U$1") (pin "P$A2") (pinfunction "P$A2_P$A2") (pintype "bidirectional"))
    )
    (net (code "146") (name "unconnected-(U$1-PadP$A4)") (class "Default")
      (node (ref "U$1") (pin "P$A4") (pinfunction "P$A4_P$A4") (pintype "bidirectional"))
    )
    (net (code "147") (name "unconnected-(U$1-PadP$A5)") (class "Default")
      (node (ref "U$1") (pin "P$A5") (pinfunction "P$A5_P$A5") (pintype "bidirectional"))
    )
    (net (code "148") (name "unconnected-(U$1-PadP$A6)") (class "Default")
      (node (ref "U$1") (pin "P$A6") (pinfunction "P$A6_P$A6") (pintype "bidirectional"))
    )
    (net (code "149") (name "unconnected-(U$1-PadP$A7)") (class "Default")
      (node (ref "U$1") (pin "P$A7") (pinfunction "P$A7_P$A7") (pintype "bidirectional"))
    )
    (net (code "150") (name "unconnected-(U$1-PadP$A8)") (class "Default")
      (node (ref "U$1") (pin "P$A8") (pinfunction "P$A8_P$A8") (pintype "bidirectional"))
    )
    (net (code "151") (name "unconnected-(U$1-PadP$A9)") (class "Default")
      (node (ref "U$1") (pin "P$A9") (pinfunction "P$A9_P$A9") (pintype "bidirectional"))
    )
    (net (code "152") (name "unconnected-(U$1-PadP$A10)") (class "Default")
      (node (ref "U$1") (pin "P$A10") (pinfunction "P$A10_P$A10") (pintype "bidirectional"))
    )
    (net (code "153") (name "unconnected-(U$1-PadP$A11)") (class "Default")
      (node (ref "U$1") (pin "P$A11") (pinfunction "P$A11_P$A11") (pintype "bidirectional"))
    )
    (net (code "154") (name "unconnected-(U$1-PadP$A12)") (class "Default")
      (node (ref "U$1") (pin "P$A12") (pinfunction "P$A12_P$A12") (pintype "bidirectional"))
    )
    (net (code "155") (name "unconnected-(U$1-PadP$A13)") (class "Default")
      (node (ref "U$1") (pin "P$A13") (pinfunction "P$A13_P$A13") (pintype "bidirectional"))
    )
    (net (code "156") (name "unconnected-(U$1-PadP$A14)") (class "Default")
      (node (ref "U$1") (pin "P$A14") (pinfunction "P$A14_P$A14") (pintype "bidirectional"))
    )
    (net (code "157") (name "unconnected-(U$1-PadP$A15)") (class "Default")
      (node (ref "U$1") (pin "P$A15") (pinfunction "P$A15_P$A15") (pintype "bidirectional"))
    )
    (net (code "158") (name "unconnected-(U$1-PadP$A16)") (class "Default")
      (node (ref "U$1") (pin "P$A16") (pinfunction "P$A16_P$A16") (pintype "bidirectional"))
    )
    (net (code "159") (name "unconnected-(U$1-PadP$A17)") (class "Default")
      (node (ref "U$1") (pin "P$A17") (pinfunction "P$A17_P$A17") (pintype "bidirectional"))
    )
    (net (code "160") (name "unconnected-(U$1-PadP$A18)") (class "Default")
      (node (ref "U$1") (pin "P$A18") (pinfunction "P$A18_P$A18") (pintype "bidirectional"))
    )
    (net (code "161") (name "unconnected-(U$1-PadP$A19)") (class "Default")
      (node (ref "U$1") (pin "P$A19") (pinfunction "P$A19_P$A19") (pintype "bidirectional"))
    )
    (net (code "162") (name "unconnected-(U$1-PadP$A20)") (class "Default")
      (node (ref "U$1") (pin "P$A20") (pinfunction "P$A20_P$A20") (pintype "bidirectional"))
    )
    (net (code "163") (name "unconnected-(U$1-PadP$A21)") (class "Default")
      (node (ref "U$1") (pin "P$A21") (pinfunction "P$A21_P$A21") (pintype "bidirectional"))
    )
    (net (code "164") (name "unconnected-(U$1-PadP$A22)") (class "Default")
      (node (ref "U$1") (pin "P$A22") (pinfunction "P$A22_P$A22") (pintype "bidirectional"))
    )
    (net (code "165") (name "unconnected-(U$1-PadP$A23)") (class "Default")
      (node (ref "U$1") (pin "P$A23") (pinfunction "P$A23_P$A23") (pintype "bidirectional"))
    )
    (net (code "166") (name "unconnected-(U$1-PadP$B1)") (class "Default")
      (node (ref "U$1") (pin "P$B1") (pinfunction "P$B1_P$B1") (pintype "bidirectional"))
    )
    (net (code "167") (name "unconnected-(U$1-PadP$B2)") (class "Default")
      (node (ref "U$1") (pin "P$B2") (pinfunction "P$B2_P$B2") (pintype "bidirectional"))
    )
    (net (code "168") (name "unconnected-(U$1-PadP$B4)") (class "Default")
      (node (ref "U$1") (pin "P$B4") (pinfunction "P$B4_P$B4") (pintype "bidirectional"))
    )
    (net (code "169") (name "unconnected-(U$1-PadP$B5)") (class "Default")
      (node (ref "U$1") (pin "P$B5") (pinfunction "P$B5_P$B5") (pintype "bidirectional"))
    )
    (net (code "170") (name "unconnected-(U$1-PadP$B6)") (class "Default")
      (node (ref "U$1") (pin "P$B6") (pinfunction "P$B6_P$B6") (pintype "bidirectional"))
    )
    (net (code "171") (name "unconnected-(U$1-PadP$B7)") (class "Default")
      (node (ref "U$1") (pin "P$B7") (pinfunction "P$B7_P$B7") (pintype "bidirectional"))
    )
    (net (code "172") (name "unconnected-(U$1-PadP$B8)") (class "Default")
      (node (ref "U$1") (pin "P$B8") (pinfunction "P$B8_P$B8") (pintype "bidirectional"))
    )
    (net (code "173") (name "unconnected-(U$1-PadP$B9)") (class "Default")
      (node (ref "U$1") (pin "P$B9") (pinfunction "P$B9_P$B9") (pintype "bidirectional"))
    )
    (net (code "174") (name "unconnected-(U$1-PadP$B10)") (class "Default")
      (node (ref "U$1") (pin "P$B10") (pinfunction "P$B10_P$B10") (pintype "bidirectional"))
    )
    (net (code "175") (name "unconnected-(U$1-PadP$B11)") (class "Default")
      (node (ref "U$1") (pin "P$B11") (pinfunction "P$B11_P$B11") (pintype "bidirectional"))
    )
    (net (code "176") (name "unconnected-(U$1-PadP$B12)") (class "Default")
      (node (ref "U$1") (pin "P$B12") (pinfunction "P$B12_P$B12") (pintype "bidirectional"))
    )
    (net (code "177") (name "unconnected-(U$1-PadP$B13)") (class "Default")
      (node (ref "U$1") (pin "P$B13") (pinfunction "P$B13_P$B13") (pintype "bidirectional"))
    )
    (net (code "178") (name "unconnected-(U$1-PadP$B14)") (class "Default")
      (node (ref "U$1") (pin "P$B14") (pinfunction "P$B14_P$B14") (pintype "bidirectional"))
    )
    (net (code "179") (name "unconnected-(U$1-PadP$B15)") (class "Default")
      (node (ref "U$1") (pin "P$B15") (pinfunction "P$B15_P$B15") (pintype "bidirectional"))
    )
    (net (code "180") (name "unconnected-(U$1-PadP$B16)") (class "Default")
      (node (ref "U$1") (pin "P$B16") (pinfunction "P$B16_P$B16") (pintype "bidirectional"))
    )
    (net (code "181") (name "unconnected-(U$1-PadP$B17)") (class "Default")
      (node (ref "U$1") (pin "P$B17") (pinfunction "P$B17_P$B17") (pintype "bidirectional"))
    )
    (net (code "182") (name "unconnected-(U$1-PadP$B18)") (class "Default")
      (node (ref "U$1") (pin "P$B18") (pinfunction "P$B18_P$B18") (pintype "bidirectional"))
    )
    (net (code "183") (name "unconnected-(U$1-PadP$B19)") (class "Default")
      (node (ref "U$1") (pin "P$B19") (pinfunction "P$B19_P$B19") (pintype "bidirectional"))
    )
    (net (code "184") (name "unconnected-(U$1-PadP$B20)") (class "Default")
      (node (ref "U$1") (pin "P$B20") (pinfunction "P$B20_P$B20") (pintype "bidirectional"))
    )
    (net (code "185") (name "unconnected-(U$1-PadP$B21)") (class "Default")
      (node (ref "U$1") (pin "P$B21") (pinfunction "P$B21_P$B21") (pintype "bidirectional"))
    )
    (net (code "186") (name "unconnected-(U$1-PadP$B22)") (class "Default")
      (node (ref "U$1") (pin "P$B22") (pinfunction "P$B22_P$B22") (pintype "bidirectional"))
    )
    (net (code "187") (name "unconnected-(U$1-PadP$B23)") (class "Default")
      (node (ref "U$1") (pin "P$B23") (pinfunction "P$B23_P$B23") (pintype "bidirectional"))
    )
    (net (code "188") (name "unconnected-(U$2-0(RX)-PadRX)") (class "Default")
      (node (ref "U$2") (pin "RX") (pinfunction "0(RX)_RX") (pintype "bidirectional"))
    )
    (net (code "189") (name "unconnected-(U$2-1(TX)-PadTX)") (class "Default")
      (node (ref "U$2") (pin "TX") (pinfunction "1(TX)_TX") (pintype "bidirectional"))
    )
    (net (code "190") (name "unconnected-(U$2-3.3V-Pad3V3_1)") (class "Default")
      (node (ref "U$2") (pin "3V3_1") (pinfunction "3.3V_3V3_1") (pintype "bidirectional"))
    )
    (net (code "191") (name "unconnected-(U$2-3.3V..-Pad3V3_2)") (class "Default")
      (node (ref "U$2") (pin "3V3_2") (pinfunction "3.3V.._3V3_2") (pintype "bidirectional"))
    )
    (net (code "192") (name "unconnected-(U$2-Pad+5V_)") (class "Default")
      (node (ref "U$2") (pin "+5V_") (pinfunction "+5V__+5V_") (pintype "bidirectional"))
    )
    (net (code "193") (name "unconnected-(U$2-PadAREF)") (class "Default")
      (node (ref "U$2") (pin "AREF") (pinfunction "AREF_AREF") (pintype "bidirectional"))
    )
    (net (code "194") (name "unconnected-(U$2-PadGND__)") (class "Default")
      (node (ref "U$2") (pin "GND__") (pinfunction "GND___GND__") (pintype "bidirectional"))
    )
    (net (code "195") (name "unconnected-(U$2-PadMISO)") (class "Default")
      (node (ref "U$2") (pin "MISO") (pinfunction "MISO_MISO") (pintype "bidirectional"))
    )
    (net (code "196") (name "unconnected-(U$2-PadMOSI)") (class "Default")
      (node (ref "U$2") (pin "MOSI") (pinfunction "MOSI_MOSI") (pintype "bidirectional"))
    )
    (net (code "197") (name "unconnected-(U$2-PadRESET.)") (class "Default")
      (node (ref "U$2") (pin "RESET.") (pinfunction "RESET._RESET.") (pintype "bidirectional"))
    )
    (net (code "198") (name "unconnected-(U$2-PadSCK)") (class "Default")
      (node (ref "U$2") (pin "SCK") (pinfunction "SCK_SCK") (pintype "bidirectional"))
    )
  )
)
